# zero_crossing.net
KiCad netlist of a schematic drawn in EAGLE
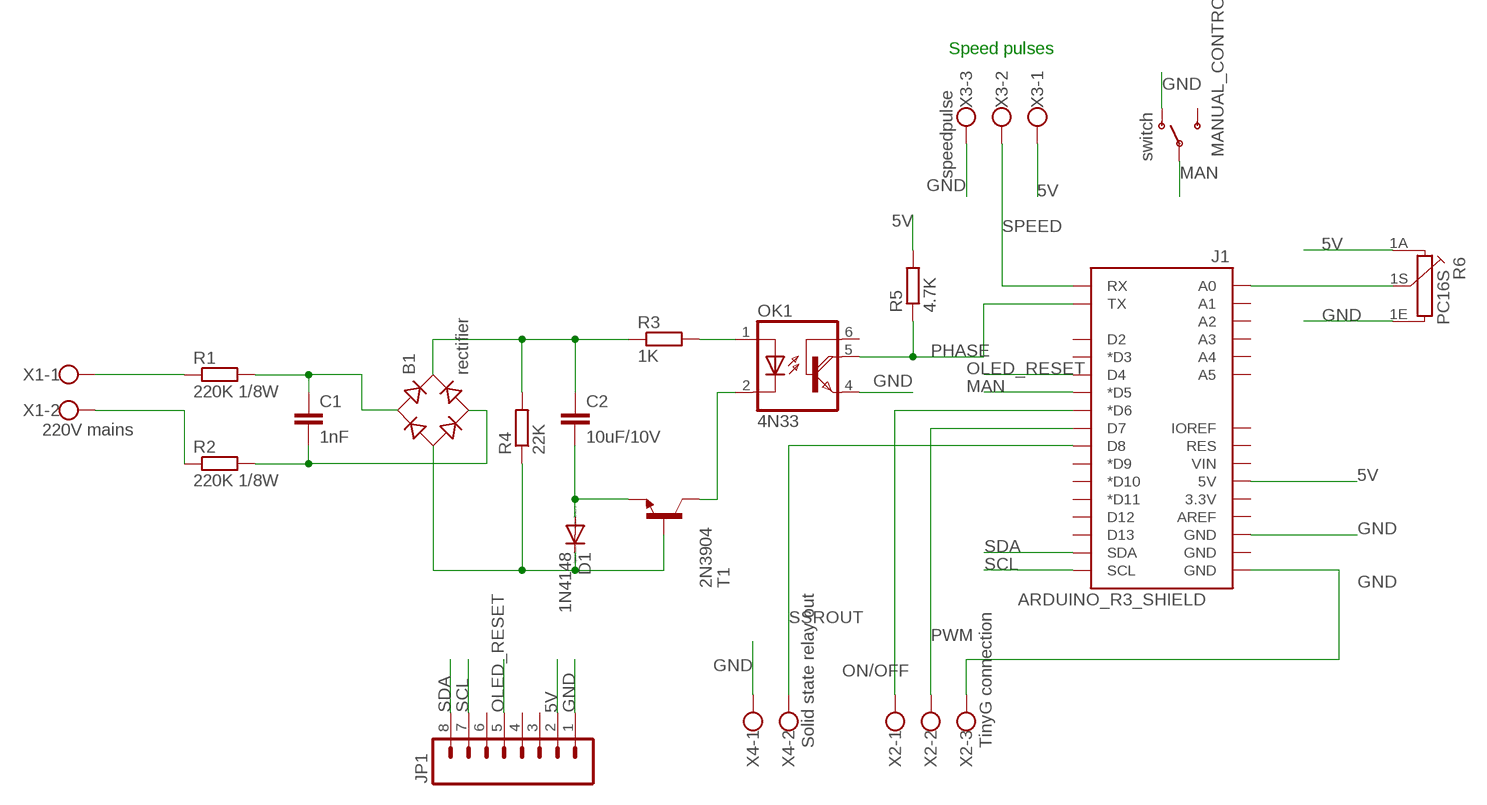
[diagram p0: schematic, sheet 1]

(export (version "E")
  (design (tool "Eeschema 10.0.6"))
  (components
    (comp (ref "B1")
      (value "rectifier")
      (footprint "eagle-import:RB1A")
      (libsource (lib "eagle-import") (part "RB1A"))
    )
    (comp (ref "C1")
      (value "1nF")
      (footprint "eagle-import:C050-025X075")
      (libsource (lib "eagle-import") (part "C-EU050-025X075"))
    )
    (comp (ref "C2")
      (value "10uF/10V")
      (footprint "eagle-import:C050-025X075")
      (libsource (lib "eagle-import") (part "C-EU050-025X075"))
    )
    (comp (ref "D1")
      (value "1N4148")
      (footprint "eagle-import:DO35-7")
      (libsource (lib "eagle-import") (part "1N4148DO35-7"))
    )
    (comp (ref "J1")
      (value "ARDUINO_R3_SHIELD")
      (footprint "eagle-import:UNO_R3_SHIELD")
      (libsource (lib "eagle-import") (part "ARDUINO_R3_SHIELD"))
    )
    (comp (ref "JP1")
      (value "M08LOCK_LONGPADS")
      (footprint "eagle-import:1X08_LOCK_LONGPADS")
      (libsource (lib "eagle-import") (part "M08LOCK_LONGPADS"))
    )
    (comp (ref "MANUAL_CONTROL")
      (value "switch")
      (footprint "eagle-import:SWITCH-SPDT")
      (libsource (lib "eagle-import") (part "SWITCH-SPDTPTH"))
    )
    (comp (ref "OK1")
      (value "4N33")
      (footprint "eagle-import:DIL06")
      (fields (field (name "MF") "VISHAY/TELEFUNKEN"))
      (libsource (lib "eagle-import") (part "4N33"))
    )
    (comp (ref "R1")
      (value "220K 1/8W")
      (footprint "eagle-import:0207_10")
      (libsource (lib "eagle-import") (part "R-EU_0207/10"))
    )
    (comp (ref "R2")
      (value "220K 1/8W")
      (footprint "eagle-import:0207_10")
      (libsource (lib "eagle-import") (part "R-EU_0207/10"))
    )
    (comp (ref "R3")
      (value "1K")
      (footprint "eagle-import:0207_10")
      (libsource (lib "eagle-import") (part "R-EU_0207/10"))
    )
    (comp (ref "R4")
      (value "22K")
      (footprint "eagle-import:0207_10")
      (libsource (lib "eagle-import") (part "R-EU_0207/10"))
    )
    (comp (ref "R5")
      (value "4.7K")
      (footprint "eagle-import:0207_10")
      (libsource (lib "eagle-import") (part "R-EU_0207/10"))
    )
    (comp (ref "R6")
      (value "PC16S")
      (footprint "eagle-import:PC16S")
      (libsource (lib "eagle-import") (part "PC16S"))
    )
    (comp (ref "T1")
      (value "2N3904")
      (footprint "eagle-import:TO92-ECB")
      (libsource (lib "eagle-import") (part "2SC458"))
    )
    (comp (ref "X1")
      (value "220V mains")
      (footprint "eagle-import:W237-102")
      (fields (field (name "MPN") "237-102"))
      (libsource (lib "eagle-import") (part "W237-102"))
    )
    (comp (ref "X2")
      (value "TinyG connection")
      (footprint "eagle-import:W237-103")
      (fields (field (name "MPN") "237-103"))
      (libsource (lib "eagle-import") (part "W237-103"))
    )
    (comp (ref "X3")
      (value "speedpulse")
      (footprint "eagle-import:W237-103")
      (fields (field (name "MPN") "237-103"))
      (libsource (lib "eagle-import") (part "W237-103"))
    )
    (comp (ref "X4")
      (value "Solid state relay out")
      (footprint "eagle-import:W237-102")
      (fields (field (name "MPN") "237-102"))
      (libsource (lib "eagle-import") (part "W237-102"))
    )
  )
  (nets
    (net (code "1") (name "/5V") (class "Default")
      (node (ref "J1") (pin "5V") (pinfunction "5V_5V") (pintype "bidirectional"))
      (node (ref "JP1") (pin "2") (pinfunction "2_2") (pintype "passive"))
      (node (ref "R5") (pin "2") (pinfunction "2_2") (pintype "passive"))
      (node (ref "R6") (pin "1A") (pinfunction "1A_1A") (pintype "passive"))
      (node (ref "X3") (pin "1") (pinfunction "KL_1") (pintype "passive"))
    )
    (net (code "2") (name "/GND") (class "Default")
      (node (ref "J1") (pin "GND@0") (pinfunction "GND_GND@0") (pintype "bidirectional"))
      (node (ref "J1") (pin "GND@2") (pinfunction "GND_GND@2") (pintype "bidirectional"))
      (node (ref "JP1") (pin "1") (pinfunction "1_1") (pintype "passive"))
      (node (ref "MANUAL_CONTROL") (pin "1") (pinfunction "O_1") (pintype "passive"))
      (node (ref "OK1") (pin "4") (pinfunction "E_4") (pintype "passive"))
      (node (ref "R6") (pin "1E") (pinfunction "1E_1E") (pintype "passive"))
      (node (ref "X2") (pin "3") (pinfunction "KL_3") (pintype "passive"))
      (node (ref "X3") (pin "3") (pinfunction "KL_3") (pintype "passive"))
      (node (ref "X4") (pin "1") (pinfunction "KL_1") (pintype "passive"))
    )
    (net (code "3") (name "/MAN") (class "Default")
      (node (ref "J1") (pin "D5") (pinfunction "*D5_D5") (pintype "bidirectional"))
      (node (ref "MANUAL_CONTROL") (pin "2") (pinfunction "P_2") (pintype "passive"))
    )
    (net (code "4") (name "/OLED_RESET") (class "Default")
      (node (ref "J1") (pin "D4") (pinfunction "D4_D4") (pintype "bidirectional"))
      (node (ref "JP1") (pin "5") (pinfunction "5_5") (pintype "passive"))
    )
    (net (code "5") (name "/ON{slash}OFF") (class "Default")
      (node (ref "J1") (pin "D6") (pinfunction "*D6_D6") (pintype "bidirectional"))
      (node (ref "X2") (pin "1") (pinfunction "KL_1") (pintype "passive"))
    )
    (net (code "6") (name "/PHASE") (class "Default")
      (node (ref "J1") (pin "TX") (pinfunction "TX_TX") (pintype "bidirectional"))
      (node (ref "OK1") (pin "5") (pinfunction "COL_5") (pintype "passive"))
      (node (ref "R5") (pin "1") (pinfunction "1_1") (pintype "passive"))
    )
    (net (code "7") (name "/PWM") (class "Default")
      (node (ref "J1") (pin "D7") (pinfunction "D7_D7") (pintype "bidirectional"))
      (node (ref "X2") (pin "2") (pinfunction "KL_2") (pintype "passive"))
    )
    (net (code "8") (name "/SCL") (class "Default")
      (node (ref "J1") (pin "SCL") (pinfunction "SCL_SCL") (pintype "bidirectional"))
      (node (ref "JP1") (pin "7") (pinfunction "7_7") (pintype "passive"))
    )
    (net (code "9") (name "/SDA") (class "Default")
      (node (ref "J1") (pin "SDA") (pinfunction "SDA_SDA") (pintype "bidirectional"))
      (node (ref "JP1") (pin "8") (pinfunction "8_8") (pintype "passive"))
    )
    (net (code "10") (name "/SPEED") (class "Default")
      (node (ref "J1") (pin "RX") (pinfunction "RX_RX") (pintype "bidirectional"))
      (node (ref "X3") (pin "2") (pinfunction "KL_2") (pintype "passive"))
    )
    (net (code "11") (name "/SSROUT") (class "Default")
      (node (ref "J1") (pin "D8") (pinfunction "D8_D8") (pintype "bidirectional"))
      (node (ref "X4") (pin "2") (pinfunction "KL_2") (pintype "passive"))
    )
    (net (code "12") (name "Net-(B1-Pad+)") (class "Default")
      (node (ref "B1") (pin "+") (pinfunction "+_+") (pintype "passive"))
      (node (ref "C2") (pin "1") (pinfunction "1_1") (pintype "passive"))
      (node (ref "R3") (pin "1") (pinfunction "1_1") (pintype "passive"))
      (node (ref "R4") (pin "2") (pinfunction "2_2") (pintype "passive"))
    )
    (net (code "13") (name "Net-(B1-Pad-)") (class "Default")
      (node (ref "B1") (pin "-") (pinfunction "-_-") (pintype "passive"))
      (node (ref "D1") (pin "C") (pinfunction "C_C") (pintype "passive"))
      (node (ref "R4") (pin "1") (pinfunction "1_1") (pintype "passive"))
      (node (ref "T1") (pin "B") (pinfunction "B_B") (pintype "passive"))
    )
    (net (code "14") (name "Net-(B1-PadAC1)") (class "Default")
      (node (ref "B1") (pin "AC1") (pinfunction "AC1_AC1") (pintype "passive"))
      (node (ref "C1") (pin "1") (pinfunction "1_1") (pintype "passive"))
      (node (ref "R1") (pin "2") (pinfunction "2_2") (pintype "passive"))
    )
    (net (code "15") (name "Net-(B1-PadAC2)") (class "Default")
      (node (ref "B1") (pin "AC2") (pinfunction "AC2_AC2") (pintype "passive"))
      (node (ref "C1") (pin "2") (pinfunction "2_2") (pintype "passive"))
      (node (ref "R2") (pin "2") (pinfunction "2_2") (pintype "passive"))
    )
    (net (code "16") (name "Net-(C2-Pad2)") (class "Default")
      (node (ref "C2") (pin "2") (pinfunction "2_2") (pintype "passive"))
      (node (ref "D1") (pin "A") (pinfunction "A_A") (pintype "passive"))
      (node (ref "T1") (pin "E") (pinfunction "E_E") (pintype "passive"))
    )
    (net (code "17") (name "Net-(J1-PadA0)") (class "Default")
      (node (ref "J1") (pin "A0") (pinfunction "A0_A0") (pintype "bidirectional"))
      (node (ref "R6") (pin "1S") (pinfunction "1S_1S") (pintype "passive"))
    )
    (net (code "18") (name "Net-(OK1-A)") (class "Default")
      (node (ref "OK1") (pin "1") (pinfunction "A_1") (pintype "passive"))
      (node (ref "R3") (pin "2") (pinfunction "2_2") (pintype "passive"))
    )
    (net (code "19") (name "Net-(OK1-C)") (class "Default")
      (node (ref "OK1") (pin "2") (pinfunction "C_2") (pintype "passive"))
      (node (ref "T1") (pin "C") (pinfunction "C_C") (pintype "passive"))
    )
    (net (code "20") (name "Net-(X1A-KL)") (class "Default")
      (node (ref "R1") (pin "1") (pinfunction "1_1") (pintype "passive"))
      (node (ref "X1") (pin "1") (pinfunction "KL_1") (pintype "passive"))
    )
    (net (code "21") (name "Net-(X1B-KL)") (class "Default")
      (node (ref "R2") (pin "1") (pinfunction "1_1") (pintype "passive"))
      (node (ref "X1") (pin "2") (pinfunction "KL_2") (pintype "passive"))
    )
    (net (code "22") (name "unconnected-(J1-*D3-PadD3)") (class "Default")
      (node (ref "J1") (pin "D3") (pinfunction "*D3_D3") (pintype "bidirectional"))
    )
    (net (code "23") (name "unconnected-(J1-*D9-PadD9)") (class "Default")
      (node (ref "J1") (pin "D9") (pinfunction "*D9_D9") (pintype "bidirectional"))
    )
    (net (code "24") (name "unconnected-(J1-*D10-PadD10)") (class "Default")
      (node (ref "J1") (pin "D10") (pinfunction "*D10_D10") (pintype "bidirectional"))
    )
    (net (code "25") (name "unconnected-(J1-*D11-PadD11)") (class "Default")
      (node (ref "J1") (pin "D11") (pinfunction "*D11_D11") (pintype "bidirectional"))
    )
    (net (code "26") (name "unconnected-(J1-GND-PadGND@1)") (class "Default")
      (node (ref "J1") (pin "GND@1") (pinfunction "GND_GND@1") (pintype "bidirectional"))
    )
    (net (code "27") (name "unconnected-(J1-Pad3.3V)") (class "Default")
      (node (ref "J1") (pin "3.3V") (pinfunction "3.3V_3.3V") (pintype "bidirectional"))
    )
    (net (code "28") (name "unconnected-(J1-PadA1)") (class "Default")
      (node (ref "J1") (pin "A1") (pinfunction "A1_A1") (pintype "bidirectional"))
    )
    (net (code "29") (name "unconnected-(J1-PadA2)") (class "Default")
      (node (ref "J1") (pin "A2") (pinfunction "A2_A2") (pintype "bidirectional"))
    )
    (net (code "30") (name "unconnected-(J1-PadA3)") (class "Default")
      (node (ref "J1") (pin "A3") (pinfunction "A3_A3") (pintype "bidirectional"))
    )
    (net (code "31") (name "unconnected-(J1-PadA4)") (class "Default")
      (node (ref "J1") (pin "A4") (pinfunction "A4_A4") (pintype "bidirectional"))
    )
    (net (code "32") (name "unconnected-(J1-PadA5)") (class "Default")
      (node (ref "J1") (pin "A5") (pinfunction "A5_A5") (pintype "bidirectional"))
    )
    (net (code "33") (name "unconnected-(J1-PadAREF)") (class "Default")
      (node (ref "J1") (pin "AREF") (pinfunction "AREF_AREF") (pintype "bidirectional"))
    )
    (net (code "34") (name "unconnected-(J1-PadD2)") (class "Default")
      (node (ref "J1") (pin "D2") (pinfunction "D2_D2") (pintype "bidirectional"))
    )
    (net (code "35") (name "unconnected-(J1-PadD12)") (class "Default")
      (node (ref "J1") (pin "D12") (pinfunction "D12_D12") (pintype "bidirectional"))
    )
    (net (code "36") (name "unconnected-(J1-PadD13)") (class "Default")
      (node (ref "J1") (pin "D13") (pinfunction "D13_D13") (pintype "bidirectional"))
    )
    (net (code "37") (name "unconnected-(J1-PadIOREF)") (class "Default")
      (node (ref "J1") (pin "IOREF") (pinfunction "IOREF_IOREF") (pintype "bidirectional"))
    )
    (net (code "38") (name "unconnected-(J1-PadRES)") (class "Default")
      (node (ref "J1") (pin "RES") (pinfunction "RES_RES") (pintype "bidirectional"))
    )
    (net (code "39") (name "unconnected-(J1-PadVIN)") (class "Default")
      (node (ref "J1") (pin "VIN") (pinfunction "VIN_VIN") (pintype "bidirectional"))
    )
    (net (code "40") (name "unconnected-(JP1-Pad3)") (class "Default")
      (node (ref "JP1") (pin "3") (pinfunction "3_3") (pintype "passive"))
    )
    (net (code "41") (name "unconnected-(JP1-Pad4)") (class "Default")
      (node (ref "JP1") (pin "4") (pinfunction "4_4") (pintype "passive"))
    )
    (net (code "42") (name "unconnected-(JP1-Pad6)") (class "Default")
      (node (ref "JP1") (pin "6") (pinfunction "6_6") (pintype "passive"))
    )
    (net (code "43") (name "unconnected-(MANUAL_CONTROL-S-Pad3)") (class "Default")
      (node (ref "MANUAL_CONTROL") (pin "3") (pinfunction "S_3") (pintype "passive"))
    )
    (net (code "44") (name "unconnected-(OK1-B-Pad6)") (class "Default")
      (node (ref "OK1") (pin "6") (pinfunction "B_6") (pintype "passive"))
    )
  )
)
